# CPLD.net
KiCad netlist of a schematic drawn in Altium Designer
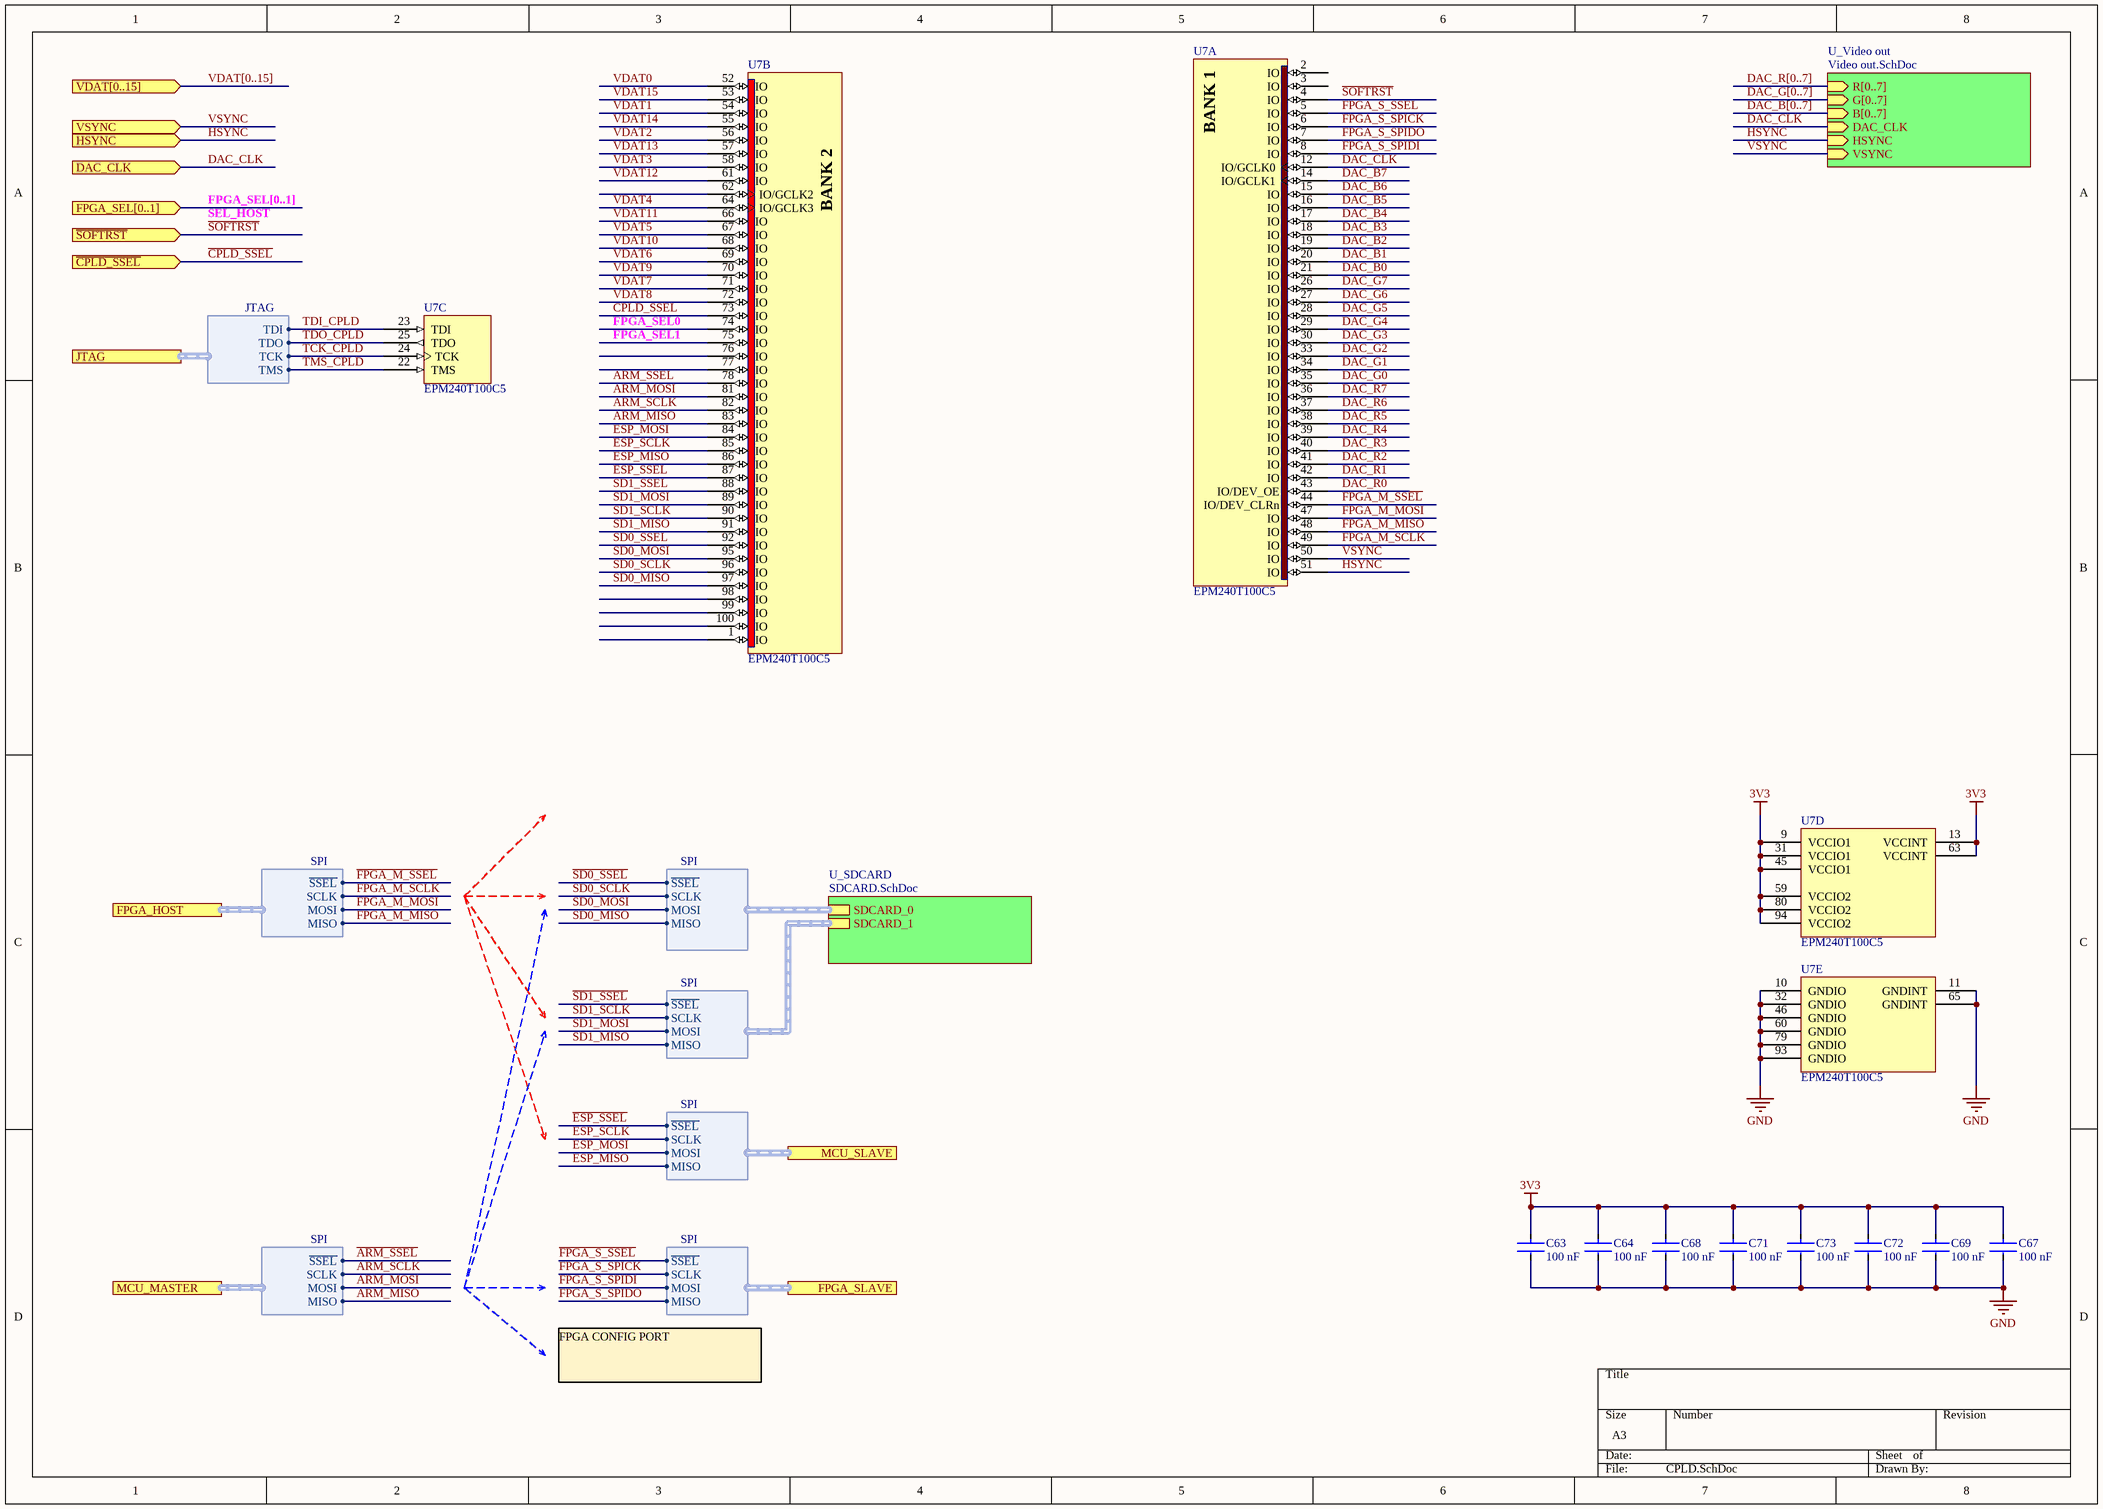
[diagram p0: CPLD.SchDoc]

(export (version "E")
  (design (tool "Eeschema 10.0.6"))
  (components
    (comp (ref "C63")
      (value "CC0805KRX7R9BB104")
      (footprint "FP-CC0805-0_85-IPC_A")
      (description "CAP CER 0.1UF 50V X7R 0805")
      (fields (field (name "MANUFACTURER") "Yageo") (field (name "CAPACITANCE") "100 nF"))
      (libsource (lib "zxevo") (part "CMP-2100-03606-3"))
    )
    (comp (ref "C64")
      (value "CC0805KRX7R9BB104")
      (footprint "FP-CC0805-0_85-IPC_A")
      (description "CAP CER 0.1UF 50V X7R 0805")
      (fields (field (name "MANUFACTURER") "Yageo") (field (name "CAPACITANCE") "100 nF"))
      (libsource (lib "zxevo") (part "CMP-2100-03606-3"))
    )
    (comp (ref "C67")
      (value "CC0805KRX7R9BB104")
      (footprint "FP-CC0805-0_85-IPC_A")
      (description "CAP CER 0.1UF 50V X7R 0805")
      (fields (field (name "MANUFACTURER") "Yageo") (field (name "CAPACITANCE") "100 nF"))
      (libsource (lib "zxevo") (part "CMP-2100-03606-3"))
    )
    (comp (ref "C68")
      (value "CC0805KRX7R9BB104")
      (footprint "FP-CC0805-0_85-IPC_A")
      (description "CAP CER 0.1UF 50V X7R 0805")
      (fields (field (name "MANUFACTURER") "Yageo") (field (name "CAPACITANCE") "100 nF"))
      (libsource (lib "zxevo") (part "CMP-2100-03606-3"))
    )
    (comp (ref "C69")
      (value "CC0805KRX7R9BB104")
      (footprint "FP-CC0805-0_85-IPC_A")
      (description "CAP CER 0.1UF 50V X7R 0805")
      (fields (field (name "MANUFACTURER") "Yageo") (field (name "CAPACITANCE") "100 nF"))
      (libsource (lib "zxevo") (part "CMP-2100-03606-3"))
    )
    (comp (ref "C71")
      (value "CC0805KRX7R9BB104")
      (footprint "FP-CC0805-0_85-IPC_A")
      (description "CAP CER 0.1UF 50V X7R 0805")
      (fields (field (name "MANUFACTURER") "Yageo") (field (name "CAPACITANCE") "100 nF"))
      (libsource (lib "zxevo") (part "CMP-2100-03606-3"))
    )
    (comp (ref "C72")
      (value "CC0805KRX7R9BB104")
      (footprint "FP-CC0805-0_85-IPC_A")
      (description "CAP CER 0.1UF 50V X7R 0805")
      (fields (field (name "MANUFACTURER") "Yageo") (field (name "CAPACITANCE") "100 nF"))
      (libsource (lib "zxevo") (part "CMP-2100-03606-3"))
    )
    (comp (ref "C73")
      (value "CC0805KRX7R9BB104")
      (footprint "FP-CC0805-0_85-IPC_A")
      (description "CAP CER 0.1UF 50V X7R 0805")
      (fields (field (name "MANUFACTURER") "Yageo") (field (name "CAPACITANCE") "100 nF"))
      (libsource (lib "zxevo") (part "CMP-2100-03606-3"))
    )
    (comp (ref "U7")
      (value "EPM240T100C5")
      (footprint "TQFP100_M")
      (fields (field (name "MANUFACTURER") "Intel Altera"))
      (libsource (lib "") (part "CMP-0144-00216-1_1"))
    )
  )
  (nets
    (net (code "3") (name "/ARM_MISO") (class "Default")
      (node (ref "U7") (pin "83") (pinfunction "IO_83") (pintype "bidirectional"))
    )
    (net (code "4") (name "/ARM_MOSI") (class "Default")
      (node (ref "U7") (pin "81") (pinfunction "IO_81") (pintype "bidirectional"))
    )
    (net (code "5") (name "/ARM_SCLK") (class "Default")
      (node (ref "U7") (pin "82") (pinfunction "IO_82") (pintype "bidirectional"))
    )
    (net (code "6") (name "/DAC_B0") (class "Default")
      (node (ref "U7") (pin "21") (pinfunction "IO_21") (pintype "bidirectional"))
    )
    (net (code "7") (name "/DAC_B1") (class "Default")
      (node (ref "U7") (pin "20") (pinfunction "IO_20") (pintype "bidirectional"))
    )
    (net (code "8") (name "/DAC_B2") (class "Default")
      (node (ref "U7") (pin "19") (pinfunction "IO_19") (pintype "bidirectional"))
    )
    (net (code "9") (name "/DAC_B3") (class "Default")
      (node (ref "U7") (pin "18") (pinfunction "IO_18") (pintype "bidirectional"))
    )
    (net (code "10") (name "/DAC_B4") (class "Default")
      (node (ref "U7") (pin "17") (pinfunction "IO_17") (pintype "bidirectional"))
    )
    (net (code "11") (name "/DAC_B5") (class "Default")
      (node (ref "U7") (pin "16") (pinfunction "IO_16") (pintype "bidirectional"))
    )
    (net (code "12") (name "/DAC_B6") (class "Default")
      (node (ref "U7") (pin "15") (pinfunction "IO_15") (pintype "bidirectional"))
    )
    (net (code "13") (name "/DAC_B7") (class "Default")
      (node (ref "U7") (pin "14") (pinfunction "IO/GCLK1_14") (pintype "bidirectional"))
    )
    (net (code "15") (name "/DAC_CLK") (class "Default")
      (node (ref "U7") (pin "12") (pinfunction "IO/GCLK0_12") (pintype "bidirectional"))
    )
    (net (code "16") (name "/DAC_G0") (class "Default")
      (node (ref "U7") (pin "35") (pinfunction "IO_35") (pintype "bidirectional"))
    )
    (net (code "17") (name "/DAC_G1") (class "Default")
      (node (ref "U7") (pin "34") (pinfunction "IO_34") (pintype "bidirectional"))
    )
    (net (code "18") (name "/DAC_G2") (class "Default")
      (node (ref "U7") (pin "33") (pinfunction "IO_33") (pintype "bidirectional"))
    )
    (net (code "19") (name "/DAC_G3") (class "Default")
      (node (ref "U7") (pin "30") (pinfunction "IO_30") (pintype "bidirectional"))
    )
    (net (code "20") (name "/DAC_G4") (class "Default")
      (node (ref "U7") (pin "29") (pinfunction "IO_29") (pintype "bidirectional"))
    )
    (net (code "21") (name "/DAC_G5") (class "Default")
      (node (ref "U7") (pin "28") (pinfunction "IO_28") (pintype "bidirectional"))
    )
    (net (code "22") (name "/DAC_G6") (class "Default")
      (node (ref "U7") (pin "27") (pinfunction "IO_27") (pintype "bidirectional"))
    )
    (net (code "23") (name "/DAC_G7") (class "Default")
      (node (ref "U7") (pin "26") (pinfunction "IO_26") (pintype "bidirectional"))
    )
    (net (code "25") (name "/DAC_R0") (class "Default")
      (node (ref "U7") (pin "43") (pinfunction "IO/DEV_OE_43") (pintype "bidirectional"))
    )
    (net (code "26") (name "/DAC_R1") (class "Default")
      (node (ref "U7") (pin "42") (pinfunction "IO_42") (pintype "bidirectional"))
    )
    (net (code "27") (name "/DAC_R2") (class "Default")
      (node (ref "U7") (pin "41") (pinfunction "IO_41") (pintype "bidirectional"))
    )
    (net (code "28") (name "/DAC_R3") (class "Default")
      (node (ref "U7") (pin "40") (pinfunction "IO_40") (pintype "bidirectional"))
    )
    (net (code "29") (name "/DAC_R4") (class "Default")
      (node (ref "U7") (pin "39") (pinfunction "IO_39") (pintype "bidirectional"))
    )
    (net (code "30") (name "/DAC_R5") (class "Default")
      (node (ref "U7") (pin "38") (pinfunction "IO_38") (pintype "bidirectional"))
    )
    (net (code "31") (name "/DAC_R6") (class "Default")
      (node (ref "U7") (pin "37") (pinfunction "IO_37") (pintype "bidirectional"))
    )
    (net (code "32") (name "/DAC_R7") (class "Default")
      (node (ref "U7") (pin "36") (pinfunction "IO_36") (pintype "bidirectional"))
    )
    (net (code "34") (name "/ESP_MISO") (class "Default")
      (node (ref "U7") (pin "86") (pinfunction "IO_86") (pintype "bidirectional"))
    )
    (net (code "35") (name "/ESP_MOSI") (class "Default")
      (node (ref "U7") (pin "84") (pinfunction "IO_84") (pintype "bidirectional"))
    )
    (net (code "36") (name "/ESP_SCLK") (class "Default")
      (node (ref "U7") (pin "85") (pinfunction "IO_85") (pintype "bidirectional"))
    )
    (net (code "37") (name "/FPGA_M_MISO") (class "Default")
      (node (ref "U7") (pin "48") (pinfunction "IO_48") (pintype "bidirectional"))
    )
    (net (code "38") (name "/FPGA_M_MOSI") (class "Default")
      (node (ref "U7") (pin "47") (pinfunction "IO_47") (pintype "bidirectional"))
    )
    (net (code "39") (name "/FPGA_M_SCLK") (class "Default")
      (node (ref "U7") (pin "49") (pinfunction "IO_49") (pintype "bidirectional"))
    )
    (net (code "40") (name "/FPGA_SEL0") (class "Default")
      (node (ref "U7") (pin "74") (pinfunction "IO_74") (pintype "bidirectional"))
    )
    (net (code "41") (name "/FPGA_SEL1") (class "Default")
      (node (ref "U7") (pin "75") (pinfunction "IO_75") (pintype "bidirectional"))
    )
    (net (code "43") (name "/FPGA_S_SPICK") (class "Default")
      (node (ref "U7") (pin "6") (pinfunction "IO_6") (pintype "bidirectional"))
    )
    (net (code "44") (name "/FPGA_S_SPIDI") (class "Default")
      (node (ref "U7") (pin "8") (pinfunction "IO_8") (pintype "bidirectional"))
    )
    (net (code "45") (name "/FPGA_S_SPIDO") (class "Default")
      (node (ref "U7") (pin "7") (pinfunction "IO_7") (pintype "bidirectional"))
    )
    (net (code "46") (name "/HSYNC") (class "Default")
      (node (ref "U7") (pin "51") (pinfunction "IO_51") (pintype "bidirectional"))
    )
    (net (code "47") (name "/SD0_MISO") (class "Default")
      (node (ref "U7") (pin "97") (pinfunction "IO_97") (pintype "bidirectional"))
    )
    (net (code "48") (name "/SD0_MOSI") (class "Default")
      (node (ref "U7") (pin "95") (pinfunction "IO_95") (pintype "bidirectional"))
    )
    (net (code "49") (name "/SD0_SCLK") (class "Default")
      (node (ref "U7") (pin "96") (pinfunction "IO_96") (pintype "bidirectional"))
    )
    (net (code "50") (name "/SD1_MISO") (class "Default")
      (node (ref "U7") (pin "91") (pinfunction "IO_91") (pintype "bidirectional"))
    )
    (net (code "51") (name "/SD1_MOSI") (class "Default")
      (node (ref "U7") (pin "89") (pinfunction "IO_89") (pintype "bidirectional"))
    )
    (net (code "52") (name "/SD1_SCLK") (class "Default")
      (node (ref "U7") (pin "90") (pinfunction "IO_90") (pintype "bidirectional"))
    )
    (net (code "54") (name "/TCK_CPLD") (class "Default")
      (node (ref "U7") (pin "24") (pinfunction "TCK_24") (pintype "input"))
    )
    (net (code "55") (name "/TDI_CPLD") (class "Default")
      (node (ref "U7") (pin "23") (pinfunction "TDI_23") (pintype "input"))
    )
    (net (code "56") (name "/TDO_CPLD") (class "Default")
      (node (ref "U7") (pin "25") (pinfunction "TDO_25") (pintype "output"))
    )
    (net (code "57") (name "/TMS_CPLD") (class "Default")
      (node (ref "U7") (pin "22") (pinfunction "TMS_22") (pintype "input"))
    )
    (net (code "58") (name "/VDAT0") (class "Default")
      (node (ref "U7") (pin "52") (pinfunction "IO_52") (pintype "bidirectional"))
    )
    (net (code "59") (name "/VDAT1") (class "Default")
      (node (ref "U7") (pin "54") (pinfunction "IO_54") (pintype "bidirectional"))
    )
    (net (code "60") (name "/VDAT2") (class "Default")
      (node (ref "U7") (pin "56") (pinfunction "IO_56") (pintype "bidirectional"))
    )
    (net (code "61") (name "/VDAT3") (class "Default")
      (node (ref "U7") (pin "58") (pinfunction "IO_58") (pintype "bidirectional"))
    )
    (net (code "62") (name "/VDAT4") (class "Default")
      (node (ref "U7") (pin "64") (pinfunction "IO/GCLK3_64") (pintype "bidirectional"))
    )
    (net (code "63") (name "/VDAT5") (class "Default")
      (node (ref "U7") (pin "67") (pinfunction "IO_67") (pintype "bidirectional"))
    )
    (net (code "64") (name "/VDAT6") (class "Default")
      (node (ref "U7") (pin "69") (pinfunction "IO_69") (pintype "bidirectional"))
    )
    (net (code "65") (name "/VDAT7") (class "Default")
      (node (ref "U7") (pin "71") (pinfunction "IO_71") (pintype "bidirectional"))
    )
    (net (code "66") (name "/VDAT8") (class "Default")
      (node (ref "U7") (pin "72") (pinfunction "IO_72") (pintype "bidirectional"))
    )
    (net (code "67") (name "/VDAT9") (class "Default")
      (node (ref "U7") (pin "70") (pinfunction "IO_70") (pintype "bidirectional"))
    )
    (net (code "68") (name "/VDAT10") (class "Default")
      (node (ref "U7") (pin "68") (pinfunction "IO_68") (pintype "bidirectional"))
    )
    (net (code "69") (name "/VDAT11") (class "Default")
      (node (ref "U7") (pin "66") (pinfunction "IO_66") (pintype "bidirectional"))
    )
    (net (code "70") (name "/VDAT12") (class "Default")
      (node (ref "U7") (pin "61") (pinfunction "IO_61") (pintype "bidirectional"))
    )
    (net (code "71") (name "/VDAT13") (class "Default")
      (node (ref "U7") (pin "57") (pinfunction "IO_57") (pintype "bidirectional"))
    )
    (net (code "72") (name "/VDAT14") (class "Default")
      (node (ref "U7") (pin "55") (pinfunction "IO_55") (pintype "bidirectional"))
    )
    (net (code "73") (name "/VDAT15") (class "Default")
      (node (ref "U7") (pin "53") (pinfunction "IO_53") (pintype "bidirectional"))
    )
    (net (code "75") (name "/VSYNC") (class "Default")
      (node (ref "U7") (pin "50") (pinfunction "IO_50") (pintype "bidirectional"))
    )
    (net (code "78") (name "/~{ARM_SSEL}") (class "Default")
      (node (ref "U7") (pin "78") (pinfunction "IO_78") (pintype "bidirectional"))
    )
    (net (code "79") (name "/~{CPLD_SSEL}") (class "Default")
      (node (ref "U7") (pin "73") (pinfunction "IO_73") (pintype "bidirectional"))
    )
    (net (code "80") (name "/~{ESP_SSEL}") (class "Default")
      (node (ref "U7") (pin "87") (pinfunction "IO_87") (pintype "bidirectional"))
    )
    (net (code "81") (name "/~{FPGA_M_SSEL}") (class "Default")
      (node (ref "U7") (pin "44") (pinfunction "IO/DEV_CLRn_44") (pintype "bidirectional"))
    )
    (net (code "82") (name "/~{FPGA_S_SSEL}") (class "Default")
      (node (ref "U7") (pin "5") (pinfunction "IO_5") (pintype "bidirectional"))
    )
    (net (code "83") (name "/~{SD0_SSEL}") (class "Default")
      (node (ref "U7") (pin "92") (pinfunction "IO_92") (pintype "bidirectional"))
    )
    (net (code "84") (name "/~{SD1_SSEL}") (class "Default")
      (node (ref "U7") (pin "88") (pinfunction "IO_88") (pintype "bidirectional"))
    )
    (net (code "85") (name "/~{SOFTRST}") (class "Default")
      (node (ref "U7") (pin "4") (pinfunction "IO_4") (pintype "bidirectional"))
    )
    (net (code "86") (name "3V3") (class "Default")
      (node (ref "C63") (pin "1") (pinfunction "1_1") (pintype "passive"))
      (node (ref "C64") (pin "1") (pinfunction "1_1") (pintype "passive"))
      (node (ref "C67") (pin "1") (pinfunction "1_1") (pintype "passive"))
      (node (ref "C68") (pin "1") (pinfunction "1_1") (pintype "passive"))
      (node (ref "C69") (pin "1") (pinfunction "1_1") (pintype "passive"))
      (node (ref "C71") (pin "1") (pinfunction "1_1") (pintype "passive"))
      (node (ref "C72") (pin "1") (pinfunction "1_1") (pintype "passive"))
      (node (ref "C73") (pin "1") (pinfunction "1_1") (pintype "passive"))
      (node (ref "U7") (pin "13") (pinfunction "VCCINT_13") (pintype "power_in"))
      (node (ref "U7") (pin "31") (pinfunction "VCCIO1_31") (pintype "power_in"))
      (node (ref "U7") (pin "45") (pinfunction "VCCIO1_45") (pintype "power_in"))
      (node (ref "U7") (pin "59") (pinfunction "VCCIO2_59") (pintype "power_in"))
      (node (ref "U7") (pin "63") (pinfunction "VCCINT_63") (pintype "power_in"))
      (node (ref "U7") (pin "80") (pinfunction "VCCIO2_80") (pintype "power_in"))
      (node (ref "U7") (pin "9") (pinfunction "VCCIO1_9") (pintype "power_in"))
      (node (ref "U7") (pin "94") (pinfunction "VCCIO2_94") (pintype "power_in"))
    )
    (net (code "87") (name "GND") (class "Default")
      (node (ref "C63") (pin "2") (pinfunction "2_2") (pintype "passive"))
      (node (ref "C64") (pin "2") (pinfunction "2_2") (pintype "passive"))
      (node (ref "C67") (pin "2") (pinfunction "2_2") (pintype "passive"))
      (node (ref "C68") (pin "2") (pinfunction "2_2") (pintype "passive"))
      (node (ref "C69") (pin "2") (pinfunction "2_2") (pintype "passive"))
      (node (ref "C71") (pin "2") (pinfunction "2_2") (pintype "passive"))
      (node (ref "C72") (pin "2") (pinfunction "2_2") (pintype "passive"))
      (node (ref "C73") (pin "2") (pinfunction "2_2") (pintype "passive"))
      (node (ref "U7") (pin "10") (pinfunction "GNDIO_10") (pintype "power_in"))
      (node (ref "U7") (pin "11") (pinfunction "GNDINT_11") (pintype "power_in"))
      (node (ref "U7") (pin "32") (pinfunction "GNDIO_32") (pintype "power_in"))
      (node (ref "U7") (pin "46") (pinfunction "GNDIO_46") (pintype "power_in"))
      (node (ref "U7") (pin "60") (pinfunction "GNDIO_60") (pintype "power_in"))
      (node (ref "U7") (pin "65") (pinfunction "GNDINT_65") (pintype "power_in"))
      (node (ref "U7") (pin "79") (pinfunction "GNDIO_79") (pintype "power_in"))
      (node (ref "U7") (pin "93") (pinfunction "GNDIO_93") (pintype "power_in"))
    )
    (net (code "88") (name "unconnected-(U7A-IO-Pad2)") (class "Default")
      (node (ref "U7") (pin "2") (pinfunction "IO_2") (pintype "bidirectional"))
    )
    (net (code "89") (name "unconnected-(U7A-IO-Pad3)") (class "Default")
      (node (ref "U7") (pin "3") (pinfunction "IO_3") (pintype "bidirectional"))
    )
    (net (code "90") (name "unconnected-(U7B-IO-Pad1)") (class "Default")
      (node (ref "U7") (pin "1") (pinfunction "IO_1") (pintype "bidirectional"))
    )
    (net (code "91") (name "unconnected-(U7B-IO-Pad76)") (class "Default")
      (node (ref "U7") (pin "76") (pinfunction "IO_76") (pintype "bidirectional"))
    )
    (net (code "92") (name "unconnected-(U7B-IO-Pad77)") (class "Default")
      (node (ref "U7") (pin "77") (pinfunction "IO_77") (pintype "bidirectional"))
    )
    (net (code "93") (name "unconnected-(U7B-IO-Pad98)") (class "Default")
      (node (ref "U7") (pin "98") (pinfunction "IO_98") (pintype "bidirectional"))
    )
    (net (code "94") (name "unconnected-(U7B-IO-Pad99)") (class "Default")
      (node (ref "U7") (pin "99") (pinfunction "IO_99") (pintype "bidirectional"))
    )
    (net (code "95") (name "unconnected-(U7B-IO-Pad100)") (class "Default")
      (node (ref "U7") (pin "100") (pinfunction "IO_100") (pintype "bidirectional"))
    )
    (net (code "96") (name "unconnected-(U7B-IO{slash}GCLK2-Pad62)") (class "Default")
      (node (ref "U7") (pin "62") (pinfunction "IO/GCLK2_62") (pintype "bidirectional"))
    )
  )
)
